# RAM_LPDDR4.net
KiCad netlist of a schematic drawn in Altium Designer
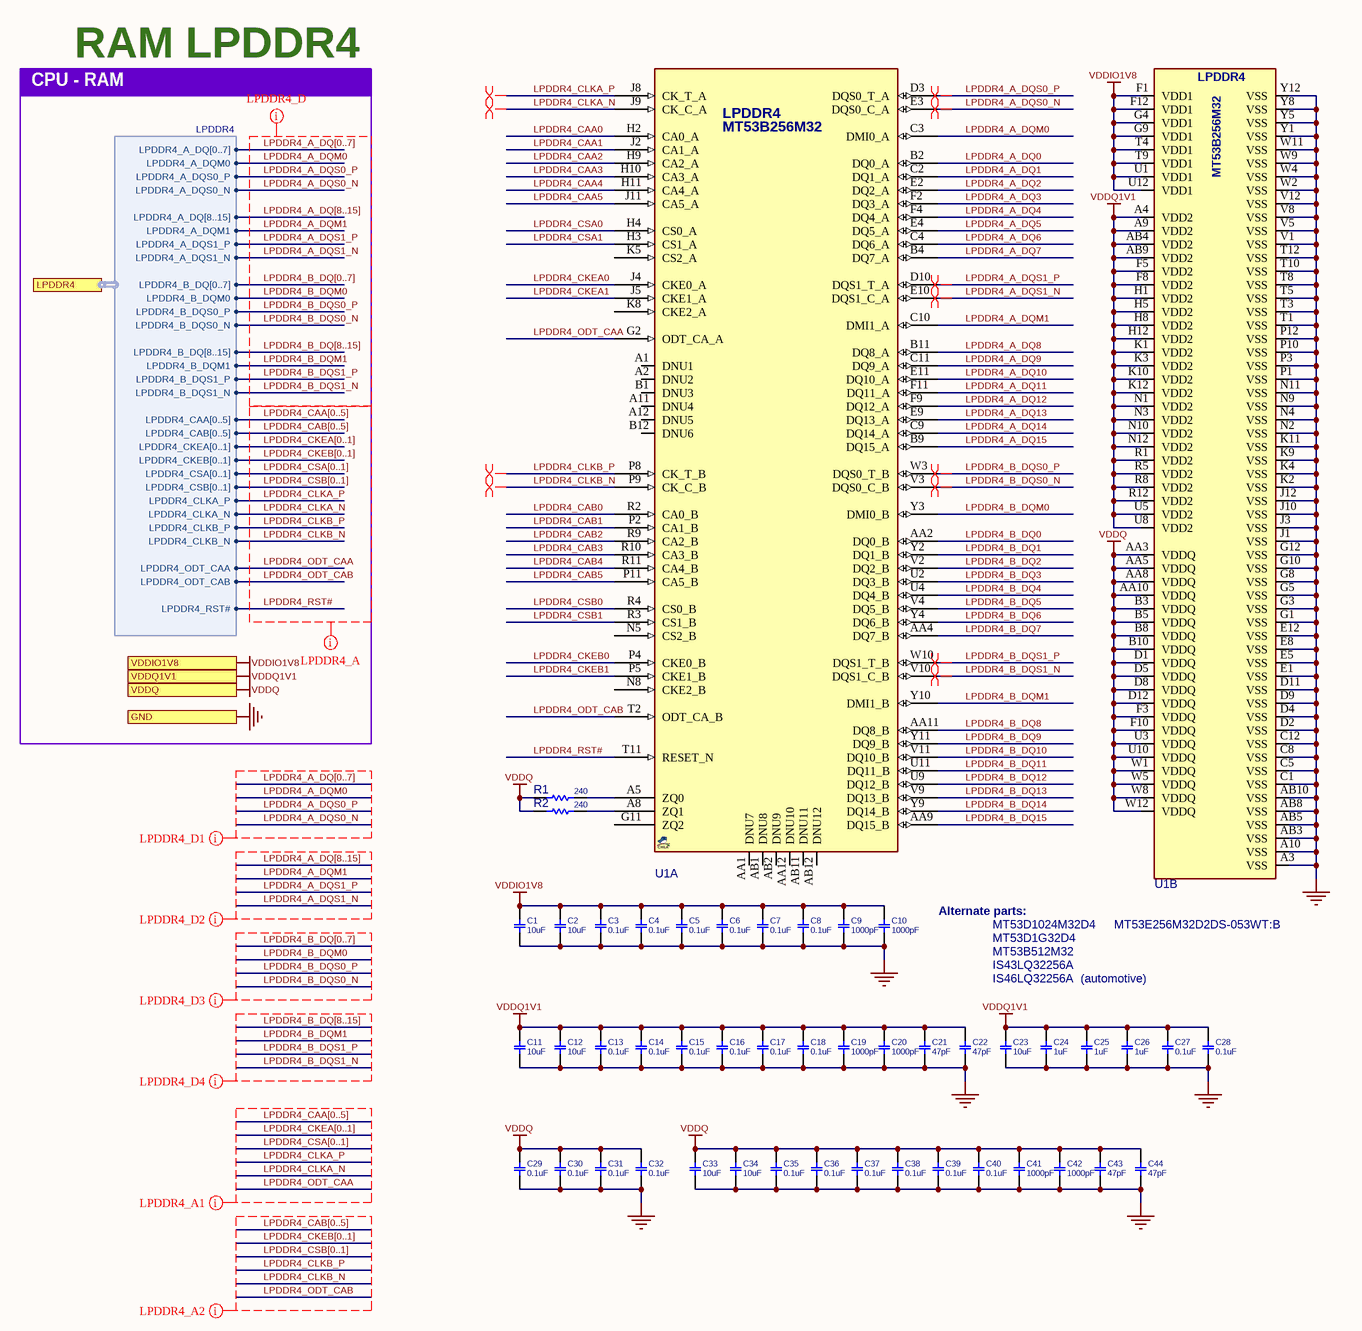
[diagram p0: RAM_LPDDR4.SchDoc]

(export (version "E")
  (design (tool "Eeschema 10.0.6"))
  (components
    (comp (ref "C1")
      (value "10uF")
      (footprint "C0402A")
      (description "CAP, MLCC")
      (fields (field (name "MANF_P#") "CL05A106MP5NUNC") (field (name "MANF") "Samsung"))
      (libsource (lib "passive_smd") (part "CAP_SMD_MLCC"))
    )
    (comp (ref "C2")
      (value "10uF")
      (footprint "C0402A")
      (description "CAP, MLCC")
      (fields (field (name "MANF_P#") "CL05A106MP5NUNC") (field (name "MANF") "Samsung"))
      (libsource (lib "passive_smd") (part "CAP_SMD_MLCC"))
    )
    (comp (ref "C3")
      (value "0.1uF")
      (footprint "C0402A")
      (description "CAP, MLCC")
      (fields (field (name "MANF_P#") "GRM155R61E104") (field (name "MANF") "Murata"))
      (libsource (lib "passive_smd") (part "CAP_SMD_MLCC"))
    )
    (comp (ref "C4")
      (value "0.1uF")
      (footprint "C0402A")
      (description "CAP, MLCC")
      (fields (field (name "MANF_P#") "GRM155R61E104") (field (name "MANF") "Murata"))
      (libsource (lib "passive_smd") (part "CAP_SMD_MLCC"))
    )
    (comp (ref "C5")
      (value "0.1uF")
      (footprint "C0402A")
      (description "CAP, MLCC")
      (fields (field (name "MANF_P#") "GRM155R61E104") (field (name "MANF") "Murata"))
      (libsource (lib "passive_smd") (part "CAP_SMD_MLCC"))
    )
    (comp (ref "C6")
      (value "0.1uF")
      (footprint "C0402A")
      (description "CAP, MLCC")
      (fields (field (name "MANF_P#") "GRM155R61E104") (field (name "MANF") "Murata"))
      (libsource (lib "passive_smd") (part "CAP_SMD_MLCC"))
    )
    (comp (ref "C7")
      (value "0.1uF")
      (footprint "C0402A")
      (description "CAP, MLCC")
      (fields (field (name "MANF_P#") "GRM155R61E104") (field (name "MANF") "Murata"))
      (libsource (lib "passive_smd") (part "CAP_SMD_MLCC"))
    )
    (comp (ref "C8")
      (value "0.1uF")
      (footprint "C0402A")
      (description "CAP, MLCC")
      (fields (field (name "MANF_P#") "GRM155R61E104") (field (name "MANF") "Murata"))
      (libsource (lib "passive_smd") (part "CAP_SMD_MLCC"))
    )
    (comp (ref "C9")
      (value "1000pF")
      (footprint "C0402A")
      (description "CAP, MLCC")
      (fields (field (name "MANF_P#") "CC0402JRNPO9BN102") (field (name "MANF") "Yageo"))
      (libsource (lib "passive_smd") (part "CAP_SMD_MLCC"))
    )
    (comp (ref "C10")
      (value "1000pF")
      (footprint "C0402A")
      (description "CAP, MLCC")
      (fields (field (name "MANF_P#") "CC0402JRNPO9BN102") (field (name "MANF") "Yageo"))
      (libsource (lib "passive_smd") (part "CAP_SMD_MLCC"))
    )
    (comp (ref "C11")
      (value "10uF")
      (footprint "C0402A")
      (description "CAP, MLCC")
      (fields (field (name "MANF_P#") "CL05A106MP5NUNC") (field (name "MANF") "Samsung"))
      (libsource (lib "passive_smd") (part "CAP_SMD_MLCC"))
    )
    (comp (ref "C12")
      (value "10uF")
      (footprint "C0402A")
      (description "CAP, MLCC")
      (fields (field (name "MANF_P#") "CL05A106MP5NUNC") (field (name "MANF") "Samsung"))
      (libsource (lib "passive_smd") (part "CAP_SMD_MLCC"))
    )
    (comp (ref "C13")
      (value "0.1uF")
      (footprint "C0402A")
      (description "CAP, MLCC")
      (fields (field (name "MANF_P#") "GRM155R61E104") (field (name "MANF") "Murata"))
      (libsource (lib "passive_smd") (part "CAP_SMD_MLCC"))
    )
    (comp (ref "C14")
      (value "0.1uF")
      (footprint "C0402A")
      (description "CAP, MLCC")
      (fields (field (name "MANF_P#") "GRM155R61E104") (field (name "MANF") "Murata"))
      (libsource (lib "passive_smd") (part "CAP_SMD_MLCC"))
    )
    (comp (ref "C15")
      (value "0.1uF")
      (footprint "C0402A")
      (description "CAP, MLCC")
      (fields (field (name "MANF_P#") "GRM155R61E104") (field (name "MANF") "Murata"))
      (libsource (lib "passive_smd") (part "CAP_SMD_MLCC"))
    )
    (comp (ref "C16")
      (value "0.1uF")
      (footprint "C0402A")
      (description "CAP, MLCC")
      (fields (field (name "MANF_P#") "GRM155R61E104") (field (name "MANF") "Murata"))
      (libsource (lib "passive_smd") (part "CAP_SMD_MLCC"))
    )
    (comp (ref "C17")
      (value "0.1uF")
      (footprint "C0402A")
      (description "CAP, MLCC")
      (fields (field (name "MANF_P#") "GRM155R61E104") (field (name "MANF") "Murata"))
      (libsource (lib "passive_smd") (part "CAP_SMD_MLCC"))
    )
    (comp (ref "C18")
      (value "0.1uF")
      (footprint "C0402A")
      (description "CAP, MLCC")
      (fields (field (name "MANF_P#") "GRM155R61E104") (field (name "MANF") "Murata"))
      (libsource (lib "passive_smd") (part "CAP_SMD_MLCC"))
    )
    (comp (ref "C19")
      (value "1000pF")
      (footprint "C0402A")
      (description "CAP, MLCC")
      (fields (field (name "MANF_P#") "CC0402JRNPO9BN102") (field (name "MANF") "Yageo"))
      (libsource (lib "passive_smd") (part "CAP_SMD_MLCC"))
    )
    (comp (ref "C20")
      (value "1000pF")
      (footprint "C0402A")
      (description "CAP, MLCC")
      (fields (field (name "MANF_P#") "CC0402JRNPO9BN102") (field (name "MANF") "Yageo"))
      (libsource (lib "passive_smd") (part "CAP_SMD_MLCC"))
    )
    (comp (ref "C21")
      (value "47pF")
      (footprint "C0402A")
      (description "CAP, MLCC")
      (libsource (lib "passive_smd") (part "CAP_SMD_MLCC"))
    )
    (comp (ref "C22")
      (value "47pF")
      (footprint "C0402A")
      (description "CAP, MLCC")
      (libsource (lib "passive_smd") (part "CAP_SMD_MLCC"))
    )
    (comp (ref "C23")
      (value "10uF")
      (footprint "C0402A")
      (description "CAP, MLCC")
      (fields (field (name "MANF_P#") "CL05A106MP5NUNC") (field (name "MANF") "Samsung"))
      (libsource (lib "passive_smd") (part "CAP_SMD_MLCC"))
    )
    (comp (ref "C24")
      (value "1uF")
      (footprint "C0402A")
      (description "CAP, MLCC")
      (libsource (lib "passive_smd") (part "CAP_SMD_MLCC"))
    )
    (comp (ref "C25")
      (value "1uF")
      (footprint "C0402A")
      (description "CAP, MLCC")
      (libsource (lib "passive_smd") (part "CAP_SMD_MLCC"))
    )
    (comp (ref "C26")
      (value "1uF")
      (footprint "C0402A")
      (description "CAP, MLCC")
      (libsource (lib "passive_smd") (part "CAP_SMD_MLCC"))
    )
    (comp (ref "C27")
      (value "0.1uF")
      (footprint "C0402A")
      (description "CAP, MLCC")
      (fields (field (name "MANF_P#") "GRM155R61E104") (field (name "MANF") "Murata"))
      (libsource (lib "passive_smd") (part "CAP_SMD_MLCC"))
    )
    (comp (ref "C28")
      (value "0.1uF")
      (footprint "C0402A")
      (description "CAP, MLCC")
      (fields (field (name "MANF_P#") "GRM155R61E104") (field (name "MANF") "Murata"))
      (libsource (lib "passive_smd") (part "CAP_SMD_MLCC"))
    )
    (comp (ref "C29")
      (value "0.1uF")
      (footprint "C0402A")
      (description "CAP, MLCC")
      (fields (field (name "MANF_P#") "GRM155R61E104") (field (name "MANF") "Murata"))
      (libsource (lib "passive_smd") (part "CAP_SMD_MLCC"))
    )
    (comp (ref "C30")
      (value "0.1uF")
      (footprint "C0402A")
      (description "CAP, MLCC")
      (fields (field (name "MANF_P#") "GRM155R61E104") (field (name "MANF") "Murata"))
      (libsource (lib "passive_smd") (part "CAP_SMD_MLCC"))
    )
    (comp (ref "C31")
      (value "0.1uF")
      (footprint "C0402A")
      (description "CAP, MLCC")
      (fields (field (name "MANF_P#") "GRM155R61E104") (field (name "MANF") "Murata"))
      (libsource (lib "passive_smd") (part "CAP_SMD_MLCC"))
    )
    (comp (ref "C32")
      (value "0.1uF")
      (footprint "C0402A")
      (description "CAP, MLCC")
      (fields (field (name "MANF_P#") "GRM155R61E104") (field (name "MANF") "Murata"))
      (libsource (lib "passive_smd") (part "CAP_SMD_MLCC"))
    )
    (comp (ref "C33")
      (value "10uF")
      (footprint "C0402A")
      (description "CAP, MLCC")
      (fields (field (name "MANF_P#") "CL05A106MP5NUNC") (field (name "MANF") "Samsung"))
      (libsource (lib "passive_smd") (part "CAP_SMD_MLCC"))
    )
    (comp (ref "C34")
      (value "10uF")
      (footprint "C0402A")
      (description "CAP, MLCC")
      (fields (field (name "MANF_P#") "CL05A106MP5NUNC") (field (name "MANF") "Samsung"))
      (libsource (lib "passive_smd") (part "CAP_SMD_MLCC"))
    )
    (comp (ref "C35")
      (value "0.1uF")
      (footprint "C0402A")
      (description "CAP, MLCC")
      (fields (field (name "MANF_P#") "GRM155R61E104") (field (name "MANF") "Murata"))
      (libsource (lib "passive_smd") (part "CAP_SMD_MLCC"))
    )
    (comp (ref "C36")
      (value "0.1uF")
      (footprint "C0402A")
      (description "CAP, MLCC")
      (fields (field (name "MANF_P#") "GRM155R61E104") (field (name "MANF") "Murata"))
      (libsource (lib "passive_smd") (part "CAP_SMD_MLCC"))
    )
    (comp (ref "C37")
      (value "0.1uF")
      (footprint "C0402A")
      (description "CAP, MLCC")
      (fields (field (name "MANF_P#") "GRM155R61E104") (field (name "MANF") "Murata"))
      (libsource (lib "passive_smd") (part "CAP_SMD_MLCC"))
    )
    (comp (ref "C38")
      (value "0.1uF")
      (footprint "C0402A")
      (description "CAP, MLCC")
      (fields (field (name "MANF_P#") "GRM155R61E104") (field (name "MANF") "Murata"))
      (libsource (lib "passive_smd") (part "CAP_SMD_MLCC"))
    )
    (comp (ref "C39")
      (value "0.1uF")
      (footprint "C0402A")
      (description "CAP, MLCC")
      (fields (field (name "MANF_P#") "GRM155R61E104") (field (name "MANF") "Murata"))
      (libsource (lib "passive_smd") (part "CAP_SMD_MLCC"))
    )
    (comp (ref "C40")
      (value "0.1uF")
      (footprint "C0402A")
      (description "CAP, MLCC")
      (fields (field (name "MANF_P#") "GRM155R61E104") (field (name "MANF") "Murata"))
      (libsource (lib "passive_smd") (part "CAP_SMD_MLCC"))
    )
    (comp (ref "C41")
      (value "1000pF")
      (footprint "C0402A")
      (description "CAP, MLCC")
      (fields (field (name "MANF_P#") "CC0402JRNPO9BN102") (field (name "MANF") "Yageo"))
      (libsource (lib "passive_smd") (part "CAP_SMD_MLCC"))
    )
    (comp (ref "C42")
      (value "1000pF")
      (footprint "C0402A")
      (description "CAP, MLCC")
      (fields (field (name "MANF_P#") "CC0402JRNPO9BN102") (field (name "MANF") "Yageo"))
      (libsource (lib "passive_smd") (part "CAP_SMD_MLCC"))
    )
    (comp (ref "C43")
      (value "47pF")
      (footprint "C0402A")
      (description "CAP, MLCC")
      (libsource (lib "passive_smd") (part "CAP_SMD_MLCC"))
    )
    (comp (ref "C44")
      (value "47pF")
      (footprint "C0402A")
      (description "CAP, MLCC")
      (libsource (lib "passive_smd") (part "CAP_SMD_MLCC"))
    )
    (comp (ref "R1")
      (value "240")
      (footprint "R0402A")
      (description "RESISTOR, SMD")
      (libsource (lib "passive_smd") (part "RES_SMD"))
    )
    (comp (ref "R2")
      (value "240")
      (footprint "R0402A")
      (description "RESISTOR, SMD")
      (libsource (lib "passive_smd") (part "RES_SMD"))
    )
    (comp (ref "U1")
      (value "LPDDR4_MT53B256M32")
      (footprint "BGA65_200_11x14")
      (description "LPDDR4 SDRAM, 8Gb (256Mb X32), 200-WFBGA")
      (fields (field (name "MANF_P#") "MT53B256M32D1GZ-062 AIT:B") (field (name "MANF") "Micron Technology"))
      (libsource (lib "memory_sdram_lpddr4") (part "LPDDR4_MT53B256M32_BGA200"))
    )
  )
  (nets
    (net (code "2") (name "/LPDDR4_A_DQ0") (class "Default")
      (node (ref "U1") (pin "B2") (pinfunction "DQ0_A_B2") (pintype "bidirectional"))
    )
    (net (code "3") (name "/LPDDR4_A_DQ1") (class "Default")
      (node (ref "U1") (pin "C2") (pinfunction "DQ1_A_C2") (pintype "bidirectional"))
    )
    (net (code "4") (name "/LPDDR4_A_DQ2") (class "Default")
      (node (ref "U1") (pin "E2") (pinfunction "DQ2_A_E2") (pintype "bidirectional"))
    )
    (net (code "5") (name "/LPDDR4_A_DQ3") (class "Default")
      (node (ref "U1") (pin "F2") (pinfunction "DQ3_A_F2") (pintype "bidirectional"))
    )
    (net (code "6") (name "/LPDDR4_A_DQ4") (class "Default")
      (node (ref "U1") (pin "F4") (pinfunction "DQ4_A_F4") (pintype "bidirectional"))
    )
    (net (code "7") (name "/LPDDR4_A_DQ5") (class "Default")
      (node (ref "U1") (pin "E4") (pinfunction "DQ5_A_E4") (pintype "bidirectional"))
    )
    (net (code "8") (name "/LPDDR4_A_DQ6") (class "Default")
      (node (ref "U1") (pin "C4") (pinfunction "DQ6_A_C4") (pintype "bidirectional"))
    )
    (net (code "9") (name "/LPDDR4_A_DQ7") (class "Default")
      (node (ref "U1") (pin "B4") (pinfunction "DQ7_A_B4") (pintype "bidirectional"))
    )
    (net (code "10") (name "/LPDDR4_A_DQ8") (class "Default")
      (node (ref "U1") (pin "B11") (pinfunction "DQ8_A_B11") (pintype "bidirectional"))
    )
    (net (code "11") (name "/LPDDR4_A_DQ9") (class "Default")
      (node (ref "U1") (pin "C11") (pinfunction "DQ9_A_C11") (pintype "bidirectional"))
    )
    (net (code "12") (name "/LPDDR4_A_DQ10") (class "Default")
      (node (ref "U1") (pin "E11") (pinfunction "DQ10_A_E11") (pintype "bidirectional"))
    )
    (net (code "13") (name "/LPDDR4_A_DQ11") (class "Default")
      (node (ref "U1") (pin "F11") (pinfunction "DQ11_A_F11") (pintype "bidirectional"))
    )
    (net (code "14") (name "/LPDDR4_A_DQ12") (class "Default")
      (node (ref "U1") (pin "F9") (pinfunction "DQ12_A_F9") (pintype "bidirectional"))
    )
    (net (code "15") (name "/LPDDR4_A_DQ13") (class "Default")
      (node (ref "U1") (pin "E9") (pinfunction "DQ13_A_E9") (pintype "bidirectional"))
    )
    (net (code "16") (name "/LPDDR4_A_DQ14") (class "Default")
      (node (ref "U1") (pin "C9") (pinfunction "DQ14_A_C9") (pintype "bidirectional"))
    )
    (net (code "17") (name "/LPDDR4_A_DQ15") (class "Default")
      (node (ref "U1") (pin "B9") (pinfunction "DQ15_A_B9") (pintype "bidirectional"))
    )
    (net (code "18") (name "/LPDDR4_A_DQM0") (class "Default")
      (node (ref "U1") (pin "C3") (pinfunction "DMI0_A_C3") (pintype "bidirectional"))
    )
    (net (code "19") (name "/LPDDR4_A_DQM1") (class "Default")
      (node (ref "U1") (pin "C10") (pinfunction "DMI1_A_C10") (pintype "bidirectional"))
    )
    (net (code "20") (name "/LPDDR4_A_DQS0_N") (class "Default")
      (node (ref "U1") (pin "E3") (pinfunction "DQS0_C_A_E3") (pintype "bidirectional"))
    )
    (net (code "21") (name "/LPDDR4_A_DQS0_P") (class "Default")
      (node (ref "U1") (pin "D3") (pinfunction "DQS0_T_A_D3") (pintype "bidirectional"))
    )
    (net (code "22") (name "/LPDDR4_A_DQS1_N") (class "Default")
      (node (ref "U1") (pin "E10") (pinfunction "DQS1_C_A_E10") (pintype "bidirectional"))
    )
    (net (code "23") (name "/LPDDR4_A_DQS1_P") (class "Default")
      (node (ref "U1") (pin "D10") (pinfunction "DQS1_T_A_D10") (pintype "bidirectional"))
    )
    (net (code "26") (name "/LPDDR4_B_DQ0") (class "Default")
      (node (ref "U1") (pin "AA2") (pinfunction "DQ0_B_AA2") (pintype "bidirectional"))
    )
    (net (code "27") (name "/LPDDR4_B_DQ1") (class "Default")
      (node (ref "U1") (pin "Y2") (pinfunction "DQ1_B_Y2") (pintype "bidirectional"))
    )
    (net (code "28") (name "/LPDDR4_B_DQ2") (class "Default")
      (node (ref "U1") (pin "V2") (pinfunction "DQ2_B_V2") (pintype "bidirectional"))
    )
    (net (code "29") (name "/LPDDR4_B_DQ3") (class "Default")
      (node (ref "U1") (pin "U2") (pinfunction "DQ3_B_U2") (pintype "bidirectional"))
    )
    (net (code "30") (name "/LPDDR4_B_DQ4") (class "Default")
      (node (ref "U1") (pin "U4") (pinfunction "DQ4_B_U4") (pintype "bidirectional"))
    )
    (net (code "31") (name "/LPDDR4_B_DQ5") (class "Default")
      (node (ref "U1") (pin "V4") (pinfunction "DQ5_B_V4") (pintype "bidirectional"))
    )
    (net (code "32") (name "/LPDDR4_B_DQ6") (class "Default")
      (node (ref "U1") (pin "Y4") (pinfunction "DQ6_B_Y4") (pintype "bidirectional"))
    )
    (net (code "33") (name "/LPDDR4_B_DQ7") (class "Default")
      (node (ref "U1") (pin "AA4") (pinfunction "DQ7_B_AA4") (pintype "bidirectional"))
    )
    (net (code "34") (name "/LPDDR4_B_DQ8") (class "Default")
      (node (ref "U1") (pin "AA11") (pinfunction "DQ8_B_AA11") (pintype "bidirectional"))
    )
    (net (code "35") (name "/LPDDR4_B_DQ9") (class "Default")
      (node (ref "U1") (pin "Y11") (pinfunction "DQ9_B_Y11") (pintype "bidirectional"))
    )
    (net (code "36") (name "/LPDDR4_B_DQ10") (class "Default")
      (node (ref "U1") (pin "V11") (pinfunction "DQ10_B_V11") (pintype "bidirectional"))
    )
    (net (code "37") (name "/LPDDR4_B_DQ11") (class "Default")
      (node (ref "U1") (pin "U11") (pinfunction "DQ11_B_U11") (pintype "bidirectional"))
    )
    (net (code "38") (name "/LPDDR4_B_DQ12") (class "Default")
      (node (ref "U1") (pin "U9") (pinfunction "DQ12_B_U9") (pintype "bidirectional"))
    )
    (net (code "39") (name "/LPDDR4_B_DQ13") (class "Default")
      (node (ref "U1") (pin "V9") (pinfunction "DQ13_B_V9") (pintype "bidirectional"))
    )
    (net (code "40") (name "/LPDDR4_B_DQ14") (class "Default")
      (node (ref "U1") (pin "Y9") (pinfunction "DQ14_B_Y9") (pintype "bidirectional"))
    )
    (net (code "41") (name "/LPDDR4_B_DQ15") (class "Default")
      (node (ref "U1") (pin "AA9") (pinfunction "DQ15_B_AA9") (pintype "bidirectional"))
    )
    (net (code "42") (name "/LPDDR4_B_DQM0") (class "Default")
      (node (ref "U1") (pin "Y3") (pinfunction "DMI0_B_Y3") (pintype "bidirectional"))
    )
    (net (code "43") (name "/LPDDR4_B_DQM1") (class "Default")
      (node (ref "U1") (pin "Y10") (pinfunction "DMI1_B_Y10") (pintype "bidirectional"))
    )
    (net (code "44") (name "/LPDDR4_B_DQS0_N") (class "Default")
      (node (ref "U1") (pin "V3") (pinfunction "DQS0_C_B_V3") (pintype "bidirectional"))
    )
    (net (code "45") (name "/LPDDR4_B_DQS0_P") (class "Default")
      (node (ref "U1") (pin "W3") (pinfunction "DQS0_T_B_W3") (pintype "bidirectional"))
    )
    (net (code "46") (name "/LPDDR4_B_DQS1_N") (class "Default")
      (node (ref "U1") (pin "V10") (pinfunction "DQS1_C_B_V10") (pintype "bidirectional"))
    )
    (net (code "47") (name "/LPDDR4_B_DQS1_P") (class "Default")
      (node (ref "U1") (pin "W10") (pinfunction "DQS1_T_B_W10") (pintype "bidirectional"))
    )
    (net (code "50") (name "/LPDDR4_CAA0") (class "Default")
      (node (ref "U1") (pin "H2") (pinfunction "CA0_A_H2") (pintype "input"))
    )
    (net (code "51") (name "/LPDDR4_CAA1") (class "Default")
      (node (ref "U1") (pin "J2") (pinfunction "CA1_A_J2") (pintype "input"))
    )
    (net (code "52") (name "/LPDDR4_CAA2") (class "Default")
      (node (ref "U1") (pin "H9") (pinfunction "CA2_A_H9") (pintype "input"))
    )
    (net (code "53") (name "/LPDDR4_CAA3") (class "Default")
      (node (ref "U1") (pin "H10") (pinfunction "CA3_A_H10") (pintype "input"))
    )
    (net (code "54") (name "/LPDDR4_CAA4") (class "Default")
      (node (ref "U1") (pin "H11") (pinfunction "CA4_A_H11") (pintype "input"))
    )
    (net (code "55") (name "/LPDDR4_CAA5") (class "Default")
      (node (ref "U1") (pin "J11") (pinfunction "CA5_A_J11") (pintype "input"))
    )
    (net (code "57") (name "/LPDDR4_CAB0") (class "Default")
      (node (ref "U1") (pin "R2") (pinfunction "CA0_B_R2") (pintype "input"))
    )
    (net (code "58") (name "/LPDDR4_CAB1") (class "Default")
      (node (ref "U1") (pin "P2") (pinfunction "CA1_B_P2") (pintype "input"))
    )
    (net (code "59") (name "/LPDDR4_CAB2") (class "Default")
      (node (ref "U1") (pin "R9") (pinfunction "CA2_B_R9") (pintype "input"))
    )
    (net (code "60") (name "/LPDDR4_CAB3") (class "Default")
      (node (ref "U1") (pin "R10") (pinfunction "CA3_B_R10") (pintype "input"))
    )
    (net (code "61") (name "/LPDDR4_CAB4") (class "Default")
      (node (ref "U1") (pin "R11") (pinfunction "CA4_B_R11") (pintype "input"))
    )
    (net (code "62") (name "/LPDDR4_CAB5") (class "Default")
      (node (ref "U1") (pin "P11") (pinfunction "CA5_B_P11") (pintype "input"))
    )
    (net (code "64") (name "/LPDDR4_CKEA0") (class "Default")
      (node (ref "U1") (pin "J4") (pinfunction "CKE0_A_J4") (pintype "input"))
    )
    (net (code "65") (name "/LPDDR4_CKEA1") (class "Default")
      (node (ref "U1") (pin "J5") (pinfunction "CKE1_A_J5") (pintype "input"))
    )
    (net (code "67") (name "/LPDDR4_CKEB0") (class "Default")
      (node (ref "U1") (pin "P4") (pinfunction "CKE0_B_P4") (pintype "input"))
    )
    (net (code "68") (name "/LPDDR4_CKEB1") (class "Default")
      (node (ref "U1") (pin "P5") (pinfunction "CKE1_B_P5") (pintype "input"))
    )
    (net (code "70") (name "/LPDDR4_CLKA_N") (class "Default")
      (node (ref "U1") (pin "J9") (pinfunction "CK_C_A_J9") (pintype "input"))
    )
    (net (code "71") (name "/LPDDR4_CLKA_P") (class "Default")
      (node (ref "U1") (pin "J8") (pinfunction "CK_T_A_J8") (pintype "input"))
    )
    (net (code "72") (name "/LPDDR4_CLKB_N") (class "Default")
      (node (ref "U1") (pin "P9") (pinfunction "CK_C_B_P9") (pintype "input"))
    )
    (net (code "73") (name "/LPDDR4_CLKB_P") (class "Default")
      (node (ref "U1") (pin "P8") (pinfunction "CK_T_B_P8") (pintype "input"))
    )
    (net (code "74") (name "/LPDDR4_CSA0") (class "Default")
      (node (ref "U1") (pin "H4") (pinfunction "CS0_A_H4") (pintype "input"))
    )
    (net (code "75") (name "/LPDDR4_CSA1") (class "Default")
      (node (ref "U1") (pin "H3") (pinfunction "CS1_A_H3") (pintype "input"))
    )
    (net (code "77") (name "/LPDDR4_CSB0") (class "Default")
      (node (ref "U1") (pin "R4") (pinfunction "CS0_B_R4") (pintype "input"))
    )
    (net (code "78") (name "/LPDDR4_CSB1") (class "Default")
      (node (ref "U1") (pin "R3") (pinfunction "CS1_B_R3") (pintype "input"))
    )
    (net (code "80") (name "/LPDDR4_ODT_CAA") (class "Default")
      (node (ref "U1") (pin "G2") (pinfunction "ODT_CA_A_G2") (pintype "input"))
    )
    (net (code "81") (name "/LPDDR4_ODT_CAB") (class "Default")
      (node (ref "U1") (pin "T2") (pinfunction "ODT_CA_B_T2") (pintype "input"))
    )
    (net (code "82") (name "/LPDDR4_RST#") (class "Default")
      (node (ref "U1") (pin "T11") (pinfunction "RESET_N_T11") (pintype "input"))
    )
    (net (code "85") (name "GND") (class "Default")
      (node (ref "C1") (pin "1") (pinfunction "1_1") (pintype "passive"))
      (node (ref "C10") (pin "1") (pinfunction "1_1") (pintype "passive"))
      (node (ref "C11") (pin "1") (pinfunction "1_1") (pintype "passive"))
      (node (ref "C12") (pin "1") (pinfunction "1_1") (pintype "passive"))
      (node (ref "C13") (pin "1") (pinfunction "1_1") (pintype "passive"))
      (node (ref "C14") (pin "1") (pinfunction "1_1") (pintype "passive"))
      (node (ref "C15") (pin "1") (pinfunction "1_1") (pintype "passive"))
      (node (ref "C16") (pin "1") (pinfunction "1_1") (pintype "passive"))
      (node (ref "C17") (pin "1") (pinfunction "1_1") (pintype "passive"))
      (node (ref "C18") (pin "1") (pinfunction "1_1") (pintype "passive"))
      (node (ref "C19") (pin "1") (pinfunction "1_1") (pintype "passive"))
      (node (ref "C2") (pin "1") (pinfunction "1_1") (pintype "passive"))
      (node (ref "C20") (pin "1") (pinfunction "1_1") (pintype "passive"))
      (node (ref "C21") (pin "1") (pinfunction "1_1") (pintype "passive"))
      (node (ref "C22") (pin "1") (pinfunction "1_1") (pintype "passive"))
      (node (ref "C23") (pin "1") (pinfunction "1_1") (pintype "passive"))
      (node (ref "C24") (pin "1") (pinfunction "1_1") (pintype "passive"))
      (node (ref "C25") (pin "1") (pinfunction "1_1") (pintype "passive"))
      (node (ref "C26") (pin "1") (pinfunction "1_1") (pintype "passive"))
      (node (ref "C27") (pin "1") (pinfunction "1_1") (pintype "passive"))
      (node (ref "C28") (pin "1") (pinfunction "1_1") (pintype "passive"))
      (node (ref "C29") (pin "1") (pinfunction "1_1") (pintype "passive"))
      (node (ref "C3") (pin "1") (pinfunction "1_1") (pintype "passive"))
      (node (ref "C30") (pin "1") (pinfunction "1_1") (pintype "passive"))
      (node (ref "C31") (pin "1") (pinfunction "1_1") (pintype "passive"))
      (node (ref "C32") (pin "1") (pinfunction "1_1") (pintype "passive"))
      (node (ref "C33") (pin "1") (pinfunction "1_1") (pintype "passive"))
      (node (ref "C34") (pin "1") (pinfunction "1_1") (pintype "passive"))
      (node (ref "C35") (pin "1") (pinfunction "1_1") (pintype "passive"))
      (node (ref "C36") (pin "1") (pinfunction "1_1") (pintype "passive"))
      (node (ref "C37") (pin "1") (pinfunction "1_1") (pintype "passive"))
      (node (ref "C38") (pin "1") (pinfunction "1_1") (pintype "passive"))
      (node (ref "C39") (pin "1") (pinfunction "1_1") (pintype "passive"))
      (node (ref "C4") (pin "1") (pinfunction "1_1") (pintype "passive"))
      (node (ref "C40") (pin "1") (pinfunction "1_1") (pintype "passive"))
      (node (ref "C41") (pin "1") (pinfunction "1_1") (pintype "passive"))
      (node (ref "C42") (pin "1") (pinfunction "1_1") (pintype "passive"))
      (node (ref "C43") (pin "1") (pinfunction "1_1") (pintype "passive"))
      (node (ref "C44") (pin "1") (pinfunction "1_1") (pintype "passive"))
      (node (ref "C5") (pin "1") (pinfunction "1_1") (pintype "passive"))
      (node (ref "C6") (pin "1") (pinfunction "1_1") (pintype "passive"))
      (node (ref "C7") (pin "1") (pinfunction "1_1") (pintype "passive"))
      (node (ref "C8") (pin "1") (pinfunction "1_1") (pintype "passive"))
      (node (ref "C9") (pin "1") (pinfunction "1_1") (pintype "passive"))
      (node (ref "U1") (pin "A10") (pinfunction "VSS_A10") (pintype "power_in"))
      (node (ref "U1") (pin "A3") (pinfunction "VSS_A3") (pintype "power_in"))
      (node (ref "U1") (pin "AB10") (pinfunction "VSS_AB10") (pintype "power_in"))
      (node (ref "U1") (pin "AB3") (pinfunction "VSS_AB3") (pintype "power_in"))
      (node (ref "U1") (pin "AB5") (pinfunction "VSS_AB5") (pintype "power_in"))
      (node (ref "U1") (pin "AB8") (pinfunction "VSS_AB8") (pintype "power_in"))
      (node (ref "U1") (pin "C1") (pinfunction "VSS_C1") (pintype "power_in"))
      (node (ref "U1") (pin "C12") (pinfunction "VSS_C12") (pintype "power_in"))
      (node (ref "U1") (pin "C5") (pinfunction "VSS_C5") (pintype "power_in"))
      (node (ref "U1") (pin "C8") (pinfunction "VSS_C8") (pintype "power_in"))
      (node (ref "U1") (pin "D11") (pinfunction "VSS_D11") (pintype "power_in"))
      (node (ref "U1") (pin "D2") (pinfunction "VSS_D2") (pintype "power_in"))
      (node (ref "U1") (pin "D4") (pinfunction "VSS_D4") (pintype "power_in"))
      (node (ref "U1") (pin "D9") (pinfunction "VSS_D9") (pintype "power_in"))
      (node (ref "U1") (pin "E1") (pinfunction "VSS_E1") (pintype "power_in"))
      (node (ref "U1") (pin "E12") (pinfunction "VSS_E12") (pintype "power_in"))
      (node (ref "U1") (pin "E5") (pinfunction "VSS_E5") (pintype "power_in"))
      (node (ref "U1") (pin "E8") (pinfunction "VSS_E8") (pintype "power_in"))
      (node (ref "U1") (pin "G1") (pinfunction "VSS_G1") (pintype "power_in"))
      (node (ref "U1") (pin "G10") (pinfunction "VSS_G10") (pintype "power_in"))
      (node (ref "U1") (pin "G12") (pinfunction "VSS_G12") (pintype "power_in"))
      (node (ref "U1") (pin "G3") (pinfunction "VSS_G3") (pintype "power_in"))
      (node (ref "U1") (pin "G5") (pinfunction "VSS_G5") (pintype "power_in"))
      (node (ref "U1") (pin "G8") (pinfunction "VSS_G8") (pintype "power_in"))
      (node (ref "U1") (pin "J1") (pinfunction "VSS_J1") (pintype "power_in"))
      (node (ref "U1") (pin "J10") (pinfunction "VSS_J10") (pintype "power_in"))
      (node (ref "U1") (pin "J12") (pinfunction "VSS_J12") (pintype "power_in"))
      (node (ref "U1") (pin "J3") (pinfunction "VSS_J3") (pintype "power_in"))
      (node (ref "U1") (pin "K11") (pinfunction "VSS_K11") (pintype "power_in"))
      (node (ref "U1") (pin "K2") (pinfunction "VSS_K2") (pintype "power_in"))
      (node (ref "U1") (pin "K4") (pinfunction "VSS_K4") (pintype "power_in"))
      (node (ref "U1") (pin "K9") (pinfunction "VSS_K9") (pintype "power_in"))
      (node (ref "U1") (pin "N11") (pinfunction "VSS_N11") (pintype "power_in"))
      (node (ref "U1") (pin "N2") (pinfunction "VSS_N2") (pintype "power_in"))
      (node (ref "U1") (pin "N4") (pinfunction "VSS_N4") (pintype "power_in"))
      (node (ref "U1") (pin "N9") (pinfunction "VSS_N9") (pintype "power_in"))
      (node (ref "U1") (pin "P1") (pinfunction "VSS_P1") (pintype "power_in"))
      (node (ref "U1") (pin "P10") (pinfunction "VSS_P10") (pintype "power_in"))
      (node (ref "U1") (pin "P12") (pinfunction "VSS_P12") (pintype "power_in"))
      (node (ref "U1") (pin "P3") (pinfunction "VSS_P3") (pintype "power_in"))
      (node (ref "U1") (pin "T1") (pinfunction "VSS_T1") (pintype "power_in"))
      (node (ref "U1") (pin "T10") (pinfunction "VSS_T10") (pintype "power_in"))
      (node (ref "U1") (pin "T12") (pinfunction "VSS_T12") (pintype "power_in"))
      (node (ref "U1") (pin "T3") (pinfunction "VSS_T3") (pintype "power_in"))
      (node (ref "U1") (pin "T5") (pinfunction "VSS_T5") (pintype "power_in"))
      (node (ref "U1") (pin "T8") (pinfunction "VSS_T8") (pintype "power_in"))
      (node (ref "U1") (pin "V1") (pinfunction "VSS_V1") (pintype "power_in"))
      (node (ref "U1") (pin "V12") (pinfunction "VSS_V12") (pintype "power_in"))
      (node (ref "U1") (pin "V5") (pinfunction "VSS_V5") (pintype "power_in"))
      (node (ref "U1") (pin "V8") (pinfunction "VSS_V8") (pintype "power_in"))
      (node (ref "U1") (pin "W11") (pinfunction "VSS_W11") (pintype "power_in"))
      (node (ref "U1") (pin "W2") (pinfunction "VSS_W2") (pintype "power_in"))
      (node (ref "U1") (pin "W4") (pinfunction "VSS_W4") (pintype "power_in"))
      (node (ref "U1") (pin "W9") (pinfunction "VSS_W9") (pintype "power_in"))
      (node (ref "U1") (pin "Y1") (pinfunction "VSS_Y1") (pintype "power_in"))
      (node (ref "U1") (pin "Y12") (pinfunction "VSS_Y12") (pintype "power_in"))
      (node (ref "U1") (pin "Y5") (pinfunction "VSS_Y5") (pintype "power_in"))
      (node (ref "U1") (pin "Y8") (pinfunction "VSS_Y8") (pintype "power_in"))
    )
    (net (code "86") (name "Net-(U1A-ZQ0)") (class "Default")
      (node (ref "R1") (pin "2") (pinfunction "2_2") (pintype "passive"))
      (node (ref "U1") (pin "A5") (pinfunction "ZQ0_A5") (pintype "passive"))
    )
    (net (code "87") (name "Net-(U1A-ZQ1)") (class "Default")
      (node (ref "R2") (pin "2") (pinfunction "2_2") (pintype "passive"))
      (node (ref "U1") (pin "A8") (pinfunction "ZQ1_A8") (pintype "passive"))
    )
    (net (code "88") (name "VDDIO1V8") (class "Default")
      (node (ref "C1") (pin "2") (pinfunction "2_2") (pintype "passive"))
      (node (ref "C10") (pin "2") (pinfunction "2_2") (pintype "passive"))
      (node (ref "C2") (pin "2") (pinfunction "2_2") (pintype "passive"))
      (node (ref "C3") (pin "2") (pinfunction "2_2") (pintype "passive"))
      (node (ref "C4") (pin "2") (pinfunction "2_2") (pintype "passive"))
      (node (ref "C5") (pin "2") (pinfunction "2_2") (pintype "passive"))
      (node (ref "C6") (pin "2") (pinfunction "2_2") (pintype "passive"))
      (node (ref "C7") (pin "2") (pinfunction "2_2") (pintype "passive"))
      (node (ref "C8") (pin "2") (pinfunction "2_2") (pintype "passive"))
      (node (ref "C9") (pin "2") (pinfunction "2_2") (pintype "passive"))
      (node (ref "U1") (pin "F1") (pinfunction "VDD1_F1") (pintype "power_in"))
      (node (ref "U1") (pin "F12") (pinfunction "VDD1_F12") (pintype "power_in"))
      (node (ref "U1") (pin "G4") (pinfunction "VDD1_G4") (pintype "power_in"))
      (node (ref "U1") (pin "G9") (pinfunction "VDD1_G9") (pintype "power_in"))
      (node (ref "U1") (pin "T4") (pinfunction "VDD1_T4") (pintype "power_in"))
      (node (ref "U1") (pin "T9") (pinfunction "VDD1_T9") (pintype "power_in"))
      (node (ref "U1") (pin "U1") (pinfunction "VDD1_U1") (pintype "power_in"))
      (node (ref "U1") (pin "U12") (pinfunction "VDD1_U12") (pintype "power_in"))
    )
    (net (code "89") (name "VDDQ") (class "Default")
      (node (ref "C29") (pin "2") (pinfunction "2_2") (pintype "passive"))
      (node (ref "C30") (pin "2") (pinfunction "2_2") (pintype "passive"))
      (node (ref "C31") (pin "2") (pinfunction "2_2") (pintype "passive"))
      (node (ref "C32") (pin "2") (pinfunction "2_2") (pintype "passive"))
      (node (ref "C33") (pin "2") (pinfunction "2_2") (pintype "passive"))
      (node (ref "C34") (pin "2") (pinfunction "2_2") (pintype "passive"))
      (node (ref "C35") (pin "2") (pinfunction "2_2") (pintype "passive"))
      (node (ref "C36") (pin "2") (pinfunction "2_2") (pintype "passive"))
      (node (ref "C37") (pin "2") (pinfunction "2_2") (pintype "passive"))
      (node (ref "C38") (pin "2") (pinfunction "2_2") (pintype "passive"))
      (node (ref "C39") (pin "2") (pinfunction "2_2") (pintype "passive"))
      (node (ref "C40") (pin "2") (pinfunction "2_2") (pintype "passive"))
      (node (ref "C41") (pin "2") (pinfunction "2_2") (pintype "passive"))
      (node (ref "C42") (pin "2") (pinfunction "2_2") (pintype "passive"))
      (node (ref "C43") (pin "2") (pinfunction "2_2") (pintype "passive"))
      (node (ref "C44") (pin "2") (pinfunction "2_2") (pintype "passive"))
      (node (ref "R1") (pin "1") (pinfunction "1_1") (pintype "passive"))
      (node (ref "R2") (pin "1") (pinfunction "1_1") (pintype "passive"))
      (node (ref "U1") (pin "AA10") (pinfunction "VDDQ_AA10") (pintype "power_in"))
      (node (ref "U1") (pin "AA3") (pinfunction "VDDQ_AA3") (pintype "power_in"))
      (node (ref "U1") (pin "AA5") (pinfunction "VDDQ_AA5") (pintype "power_in"))
      (node (ref "U1") (pin "AA8") (pinfunction "VDDQ_AA8") (pintype "power_in"))
      (node (ref "U1") (pin "B10") (pinfunction "VDDQ_B10") (pintype "power_in"))
      (node (ref "U1") (pin "B3") (pinfunction "VDDQ_B3") (pintype "power_in"))
      (node (ref "U1") (pin "B5") (pinfunction "VDDQ_B5") (pintype "power_in"))
      (node (ref "U1") (pin "B8") (pinfunction "VDDQ_B8") (pintype "power_in"))
      (node (ref "U1") (pin "D1") (pinfunction "VDDQ_D1") (pintype "power_in"))
      (node (ref "U1") (pin "D12") (pinfunction "VDDQ_D12") (pintype "power_in"))
      (node (ref "U1") (pin "D5") (pinfunction "VDDQ_D5") (pintype "power_in"))
      (node (ref "U1") (pin "D8") (pinfunction "VDDQ_D8") (pintype "power_in"))
      (node (ref "U1") (pin "F10") (pinfunction "VDDQ_F10") (pintype "power_in"))
      (node (ref "U1") (pin "F3") (pinfunction "VDDQ_F3") (pintype "power_in"))
      (node (ref "U1") (pin "U10") (pinfunction "VDDQ_U10") (pintype "power_in"))
      (node (ref "U1") (pin "U3") (pinfunction "VDDQ_U3") (pintype "power_in"))
      (node (ref "U1") (pin "W1") (pinfunction "VDDQ_W1") (pintype "power_in"))
      (node (ref "U1") (pin "W12") (pinfunction "VDDQ_W12") (pintype "power_in"))
      (node (ref "U1") (pin "W5") (pinfunction "VDDQ_W5") (pintype "power_in"))
      (node (ref "U1") (pin "W8") (pinfunction "VDDQ_W8") (pintype "power_in"))
    )
    (net (code "90") (name "VDDQ1V1") (class "Default")
      (node (ref "C11") (pin "2") (pinfunction "2_2") (pintype "passive"))
      (node (ref "C12") (pin "2") (pinfunction "2_2") (pintype "passive"))
      (node (ref "C13") (pin "2") (pinfunction "2_2") (pintype "passive"))
      (node (ref "C14") (pin "2") (pinfunction "2_2") (pintype "passive"))
      (node (ref "C15") (pin "2") (pinfunction "2_2") (pintype "passive"))
      (node (ref "C16") (pin "2") (pinfunction "2_2") (pintype "passive"))
      (node (ref "C17") (pin "2") (pinfunction "2_2") (pintype "passive"))
      (node (ref "C18") (pin "2") (pinfunction "2_2") (pintype "passive"))
      (node (ref "C19") (pin "2") (pinfunction "2_2") (pintype "passive"))
      (node (ref "C20") (pin "2") (pinfunction "2_2") (pintype "passive"))
      (node (ref "C21") (pin "2") (pinfunction "2_2") (pintype "passive"))
      (node (ref "C22") (pin "2") (pinfunction "2_2") (pintype "passive"))
      (node (ref "C23") (pin "2") (pinfunction "2_2") (pintype "passive"))
      (node (ref "C24") (pin "2") (pinfunction "2_2") (pintype "passive"))
      (node (ref "C25") (pin "2") (pinfunction "2_2") (pintype "passive"))
      (node (ref "C26") (pin "2") (pinfunction "2_2") (pintype "passive"))
      (node (ref "C27") (pin "2") (pinfunction "2_2") (pintype "passive"))
      (node (ref "C28") (pin "2") (pinfunction "2_2") (pintype "passive"))
      (node (ref "U1") (pin "A4") (pinfunction "VDD2_A4") (pintype "power_in"))
      (node (ref "U1") (pin "A9") (pinfunction "VDD2_A9") (pintype "power_in"))
      (node (ref "U1") (pin "AB4") (pinfunction "VDD2_AB4") (pintype "power_in"))
      (node (ref "U1") (pin "AB9") (pinfunction "VDD2_AB9") (pintype "power_in"))
      (node (ref "U1") (pin "F5") (pinfunction "VDD2_F5") (pintype "power_in"))
      (node (ref "U1") (pin "F8") (pinfunction "VDD2_F8") (pintype "power_in"))
      (node (ref "U1") (pin "H1") (pinfunction "VDD2_H1") (pintype "power_in"))
      (node (ref "U1") (pin "H12") (pinfunction "VDD2_H12") (pintype "power_in"))
      (node (ref "U1") (pin "H5") (pinfunction "VDD2_H5") (pintype "power_in"))
      (node (ref "U1") (pin "H8") (pinfunction "VDD2_H8") (pintype "power_in"))
      (node (ref "U1") (pin "K1") (pinfunction "VDD2_K1") (pintype "power_in"))
      (node (ref "U1") (pin "K10") (pinfunction "VDD2_K10") (pintype "power_in"))
      (node (ref "U1") (pin "K12") (pinfunction "VDD2_K12") (pintype "power_in"))
      (node (ref "U1") (pin "K3") (pinfunction "VDD2_K3") (pintype "power_in"))
      (node (ref "U1") (pin "N1") (pinfunction "VDD2_N1") (pintype "power_in"))
      (node (ref "U1") (pin "N10") (pinfunction "VDD2_N10") (pintype "power_in"))
      (node (ref "U1") (pin "N12") (pinfunction "VDD2_N12") (pintype "power_in"))
      (node (ref "U1") (pin "N3") (pinfunction "VDD2_N3") (pintype "power_in"))
      (node (ref "U1") (pin "R1") (pinfunction "VDD2_R1") (pintype "power_in"))
      (node (ref "U1") (pin "R12") (pinfunction "VDD2_R12") (pintype "power_in"))
      (node (ref "U1") (pin "R5") (pinfunction "VDD2_R5") (pintype "power_in"))
      (node (ref "U1") (pin "R8") (pinfunction "VDD2_R8") (pintype "power_in"))
      (node (ref "U1") (pin "U5") (pinfunction "VDD2_U5") (pintype "power_in"))
      (node (ref "U1") (pin "U8") (pinfunction "VDD2_U8") (pintype "power_in"))
    )
    (net (code "91") (name "unconnected-(U1A-CKE2_A-PadK8)") (class "Default")
      (node (ref "U1") (pin "K8") (pinfunction "CKE2_A_K8") (pintype "input"))
    )
    (net (code "92") (name "unconnected-(U1A-CKE2_B-PadN8)") (class "Default")
      (node (ref "U1") (pin "N8") (pinfunction "CKE2_B_N8") (pintype "input"))
    )
    (net (code "93") (name "unconnected-(U1A-CS2_A-PadK5)") (class "Default")
      (node (ref "U1") (pin "K5") (pinfunction "CS2_A_K5") (pintype "input"))
    )
    (net (code "94") (name "unconnected-(U1A-CS2_B-PadN5)") (class "Default")
      (node (ref "U1") (pin "N5") (pinfunction "CS2_B_N5") (pintype "input"))
    )
    (net (code "95") (name "unconnected-(U1A-DNU1-PadA1)") (class "Default")
      (node (ref "U1") (pin "A1") (pinfunction "DNU1_A1") (pintype "passive"))
    )
    (net (code "96") (name "unconnected-(U1A-DNU2-PadA2)") (class "Default")
      (node (ref "U1") (pin "A2") (pinfunction "DNU2_A2") (pintype "passive"))
    )
    (net (code "97") (name "unconnected-(U1A-DNU3-PadB1)") (class "Default")
      (node (ref "U1") (pin "B1") (pinfunction "DNU3_B1") (pintype "passive"))
    )
    (net (code "98") (name "unconnected-(U1A-DNU4-PadA11)") (class "Default")
      (node (ref "U1") (pin "A11") (pinfunction "DNU4_A11") (pintype "passive"))
    )
    (net (code "99") (name "unconnected-(U1A-DNU5-PadA12)") (class "Default")
      (node (ref "U1") (pin "A12") (pinfunction "DNU5_A12") (pintype "passive"))
    )
    (net (code "100") (name "unconnected-(U1A-DNU6-PadB12)") (class "Default")
      (node (ref "U1") (pin "B12") (pinfunction "DNU6_B12") (pintype "passive"))
    )
    (net (code "101") (name "unconnected-(U1A-DNU7-PadAA1)") (class "Default")
      (node (ref "U1") (pin "AA1") (pinfunction "DNU7_AA1") (pintype "passive"))
    )
    (net (code "102") (name "unconnected-(U1A-DNU8-PadAB1)") (class "Default")
      (node (ref "U1") (pin "AB1") (pinfunction "DNU8_AB1") (pintype "passive"))
    )
    (net (code "103") (name "unconnected-(U1A-DNU9-PadAB2)") (class "Default")
      (node (ref "U1") (pin "AB2") (pinfunction "DNU9_AB2") (pintype "passive"))
    )
    (net (code "104") (name "unconnected-(U1A-DNU10-PadAA12)") (class "Default")
      (node (ref "U1") (pin "AA12") (pinfunction "DNU10_AA12") (pintype "passive"))
    )
    (net (code "105") (name "unconnected-(U1A-DNU11-PadAB11)") (class "Default")
      (node (ref "U1") (pin "AB11") (pinfunction "DNU11_AB11") (pintype "passive"))
    )
    (net (code "106") (name "unconnected-(U1A-DNU12-PadAB12)") (class "Default")
      (node (ref "U1") (pin "AB12") (pinfunction "DNU12_AB12") (pintype "passive"))
    )
    (net (code "107") (name "unconnected-(U1A-ZQ2-PadG11)") (class "Default")
      (node (ref "U1") (pin "G11") (pinfunction "ZQ2_G11") (pintype "passive"))
    )
  )
)
